# BM_Output_Stage.net
KiCad netlist of a schematic drawn in Altium Designer
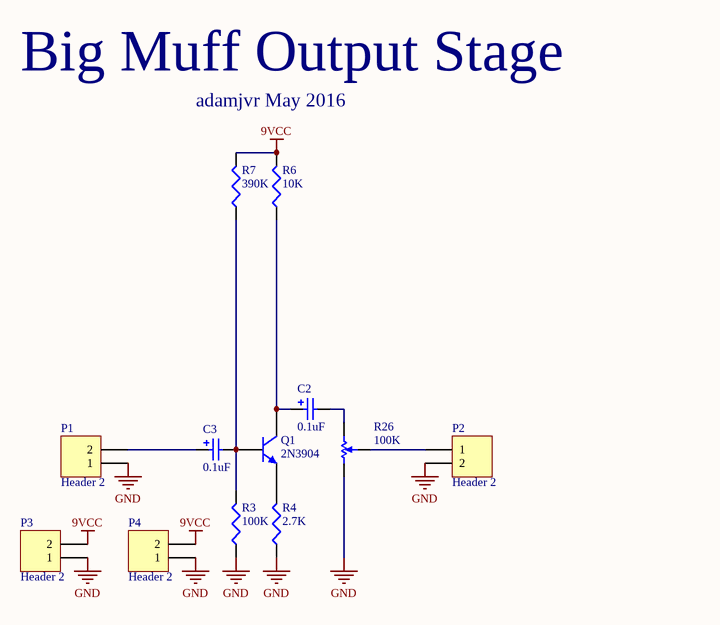
[diagram p0: BM Output Stage.SchDoc]

(export (version "E")
  (design (tool "Eeschema 10.0.6"))
  (components
    (comp (ref "C2")
      (value "0.1uF")
      (footprint "5X12.5mmCAP")
      (description "CAP ALUM 0.1UF 20% 100V RADIAL")
      (fields
        (field (name "MFR") "Nichicon")
        (field (name "TOLERANCE") "20%")
        (field (name "DESIGNER") "Adam Vadala-Roth")
      )
      (libsource (lib "AudioPartLib") (part "UFG2A0R1MDM1TD"))
    )
    (comp (ref "C3")
      (value "0.1uF")
      (footprint "5X12.5mmCAP")
      (description "CAP ALUM 0.1UF 20% 100V RADIAL")
      (fields
        (field (name "MFR") "Nichicon")
        (field (name "TOLERANCE") "20%")
        (field (name "DESIGNER") "Adam Vadala-Roth")
      )
      (libsource (lib "AudioPartLib") (part "UFG2A0R1MDM1TD"))
    )
    (comp (ref "P1")
      (value "Header 2")
      (footprint "HDR1X2")
      (description "Header, 2-Pin")
      (fields (field (name "PUBLISHER") "Altium Limited"))
      (libsource (lib "") (part "Header 2_1"))
    )
    (comp (ref "P2")
      (value "Header 2")
      (footprint "HDR1X2")
      (description "Header, 2-Pin")
      (fields (field (name "PUBLISHER") "Altium Limited"))
      (libsource (lib "Miscellaneous Connectors") (part "Header 2"))
    )
    (comp (ref "P3")
      (value "Header 2")
      (footprint "HDR1X2")
      (description "Header, 2-Pin")
      (fields (field (name "PUBLISHER") "Altium Limited"))
      (libsource (lib "") (part "Header 2_1"))
    )
    (comp (ref "P4")
      (value "Header 2")
      (footprint "HDR1X2")
      (description "Header, 2-Pin")
      (fields (field (name "PUBLISHER") "Altium Limited"))
      (libsource (lib "") (part "Header 2_1"))
    )
    (comp (ref "Q1")
      (value "2N3904")
      (footprint "TO-92A")
      (description "TRANS NPN 40V 0.2A TO-92")
      (fields
        (field (name "MFR") "Fairchild-Semiconductor")
        (field (name "VOLTAGE") "40V")
        (field (name "DESIGNER") "Adam Vadala-Roth")
      )
      (libsource (lib "AudioPartLib") (part "2N3904TF"))
    )
    (comp (ref "R3")
      (value "100K")
      (footprint "R0805")
      (description "RES SMD 100K OHM 1% 1/8W 0805")
      (fields
        (field (name "MFR") "Panasonic-Electronic-Components")
        (field (name "TOLERANCE") "1%")
        (field (name "DESIGNER") "Adam Vadala-Roth")
      )
      (libsource (lib "AudioPartLib") (part "ERJ-6ENF1003V"))
    )
    (comp (ref "R4")
      (value "2.7K")
      (footprint "R0805")
      (description "RES SMD 2.7K OHM 1% 1/8W 0805")
      (fields
        (field (name "MFR") "Samsung-Electro-Mechanics-America,-Inc.")
        (field (name "TOLERANCE") "1%")
        (field (name "DESIGNER") "Adam Vadala-Roth")
      )
      (libsource (lib "AudioPartLib") (part "RC2012F272CS"))
    )
    (comp (ref "R6")
      (value "10K")
      (footprint "R0805")
      (description "RES SMD 10K OHM 1% 1/8W 0805")
      (fields
        (field (name "MFR") "Panasonic-Electronic-Components")
        (field (name "TOLERANCE") "1%")
        (field (name "DESIGNER") "Adam Vadala-Roth")
      )
      (libsource (lib "AudioPartLib") (part "ERJ-6ENF1002V"))
    )
    (comp (ref "R7")
      (value "390K")
      (footprint "R0805")
      (description "RES SMD 390K OHM 1% 1/8W 0805")
      (fields
        (field (name "MFR") "Panasonic-Electronic-Components")
        (field (name "TOLERANCE") "1%")
        (field (name "DESIGNER") "Adam Vadala-Roth")
      )
      (libsource (lib "AudioPartLib") (part "ERJ-6ENF3903V"))
    )
    (comp (ref "R26")
      (value "100K")
      (footprint "BOURNS_PTD90SERIES_POT")
      (description "POT 100K OHM 1/20W CARBON LINEAR")
      (fields
        (field (name "MFR") "Bourns Inc.")
        (field (name "TOLERANCE") "20%")
        (field (name "DESIGNER") "Adam Vadala-Roth")
      )
      (libsource (lib "AudioPartLib") (part "PTD901-2015K-B104"))
    )
  )
  (nets
    (net (code "1") (name "9VCC") (class "Default")
      (node (ref "P3") (pin "2") (pinfunction "2_2") (pintype "passive"))
      (node (ref "P4") (pin "2") (pinfunction "2_2") (pintype "passive"))
      (node (ref "R6") (pin "2") (pinfunction "2_2") (pintype "passive"))
      (node (ref "R7") (pin "2") (pinfunction "2_2") (pintype "passive"))
    )
    (net (code "2") (name "GND") (class "Default")
      (node (ref "P1") (pin "1") (pinfunction "1_1") (pintype "passive"))
      (node (ref "P2") (pin "2") (pinfunction "2_2") (pintype "passive"))
      (node (ref "P3") (pin "1") (pinfunction "1_1") (pintype "passive"))
      (node (ref "P4") (pin "1") (pinfunction "1_1") (pintype "passive"))
      (node (ref "R26") (pin "3") (pinfunction "3_3") (pintype "passive"))
      (node (ref "R3") (pin "1") (pinfunction "1_1") (pintype "passive"))
      (node (ref "R4") (pin "1") (pinfunction "1_1") (pintype "passive"))
    )
    (net (code "3") (name "Net-(C2-Pad2)") (class "Default")
      (node (ref "C2") (pin "2") (pinfunction "2_2") (pintype "passive"))
      (node (ref "R26") (pin "1") (pinfunction "1_1") (pintype "passive"))
    )
    (net (code "4") (name "Net-(C3-Pad1)") (class "Default")
      (node (ref "C3") (pin "1") (pinfunction "1_1") (pintype "passive"))
      (node (ref "P1") (pin "2") (pinfunction "2_2") (pintype "passive"))
    )
    (net (code "5") (name "Net-(P2-Pad1)") (class "Default")
      (node (ref "P2") (pin "1") (pinfunction "1_1") (pintype "passive"))
      (node (ref "R26") (pin "2") (pinfunction "2_2") (pintype "passive"))
    )
    (net (code "6") (name "Net-(Q1-B)") (class "Default")
      (node (ref "C3") (pin "2") (pinfunction "2_2") (pintype "passive"))
      (node (ref "Q1") (pin "2") (pinfunction "B_2") (pintype "passive"))
      (node (ref "R3") (pin "2") (pinfunction "2_2") (pintype "passive"))
      (node (ref "R7") (pin "1") (pinfunction "1_1") (pintype "passive"))
    )
    (net (code "7") (name "Net-(Q1-C)") (class "Default")
      (node (ref "C2") (pin "1") (pinfunction "1_1") (pintype "passive"))
      (node (ref "Q1") (pin "3") (pinfunction "C_3") (pintype "passive"))
      (node (ref "R6") (pin "1") (pinfunction "1_1") (pintype "passive"))
    )
    (net (code "8") (name "Net-(Q1-E)") (class "Default")
      (node (ref "Q1") (pin "1") (pinfunction "E_1") (pintype "passive"))
      (node (ref "R4") (pin "2") (pinfunction "2_2") (pintype "passive"))
    )
  )
)
